# Stepper_2_0.net
KiCad netlist of a schematic drawn in EAGLE
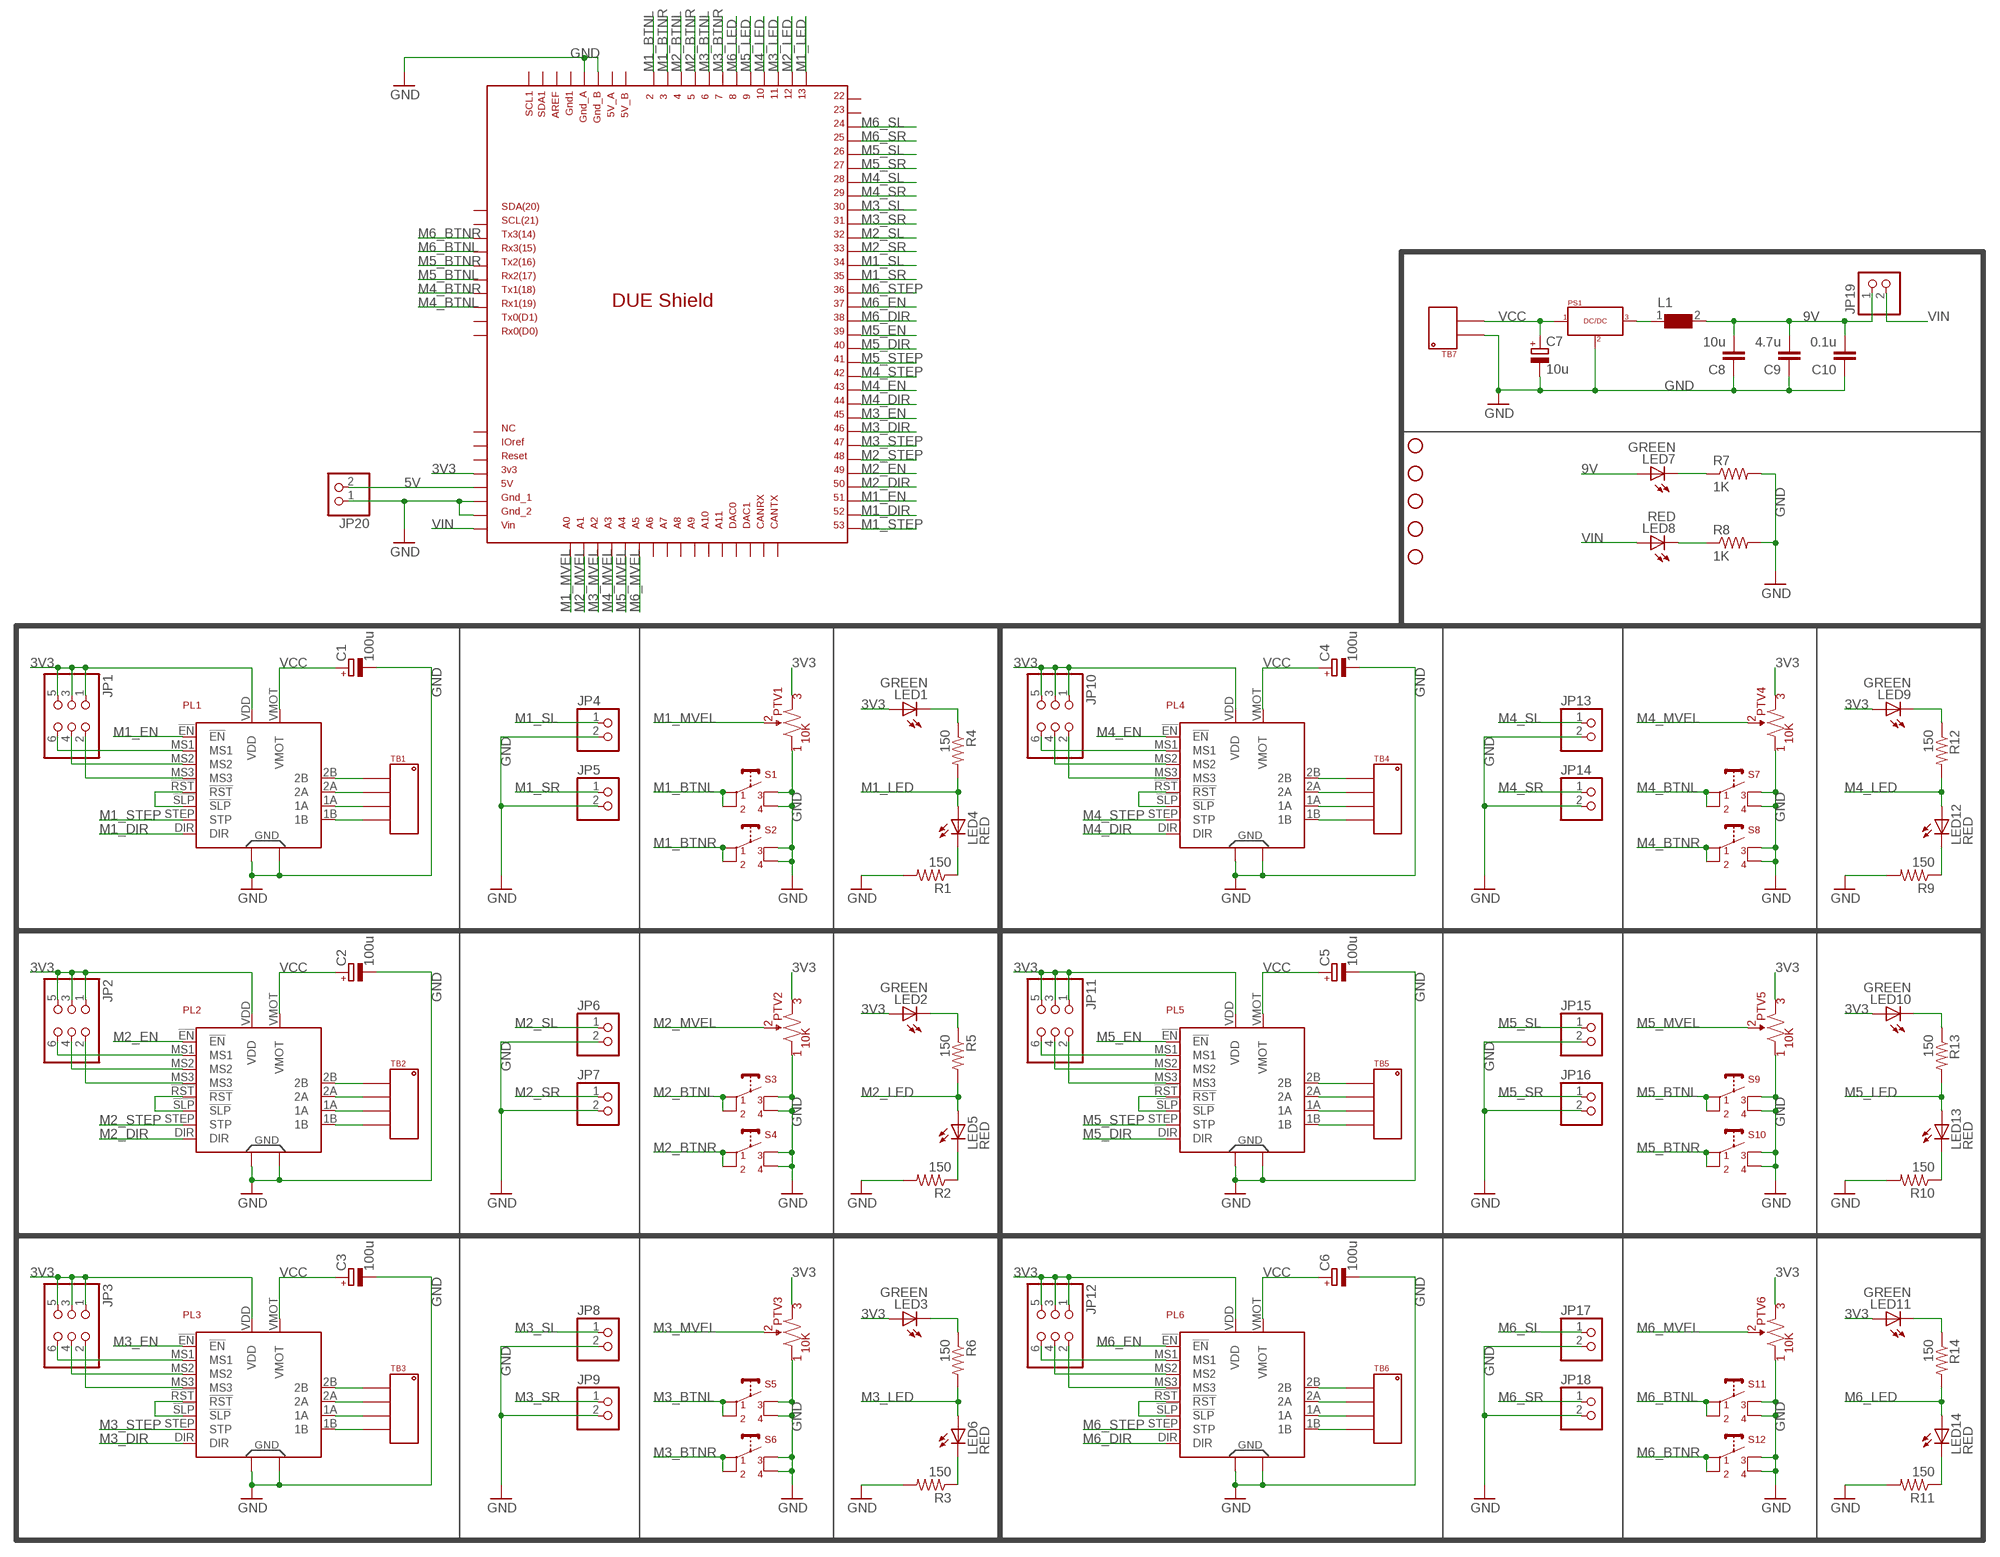
[diagram p0: schematic, sheet 1]

(export (version "E")
  (design (tool "Eeschema 10.0.6"))
  (components
    (comp (ref "C1")
      (value "100u")
      (footprint "eagle-import:ETR2")
      (libsource (lib "eagle-import") (part "CPOL-EUETR2"))
    )
    (comp (ref "C2")
      (value "100u")
      (footprint "eagle-import:ETR2")
      (libsource (lib "eagle-import") (part "CPOL-EUETR2"))
    )
    (comp (ref "C3")
      (value "100u")
      (footprint "eagle-import:ETR2")
      (libsource (lib "eagle-import") (part "CPOL-EUETR2"))
    )
    (comp (ref "C4")
      (value "100u")
      (footprint "eagle-import:ETR2")
      (libsource (lib "eagle-import") (part "CPOL-EUETR2"))
    )
    (comp (ref "C5")
      (value "100u")
      (footprint "eagle-import:ETR2")
      (libsource (lib "eagle-import") (part "CPOL-EUETR2"))
    )
    (comp (ref "C6")
      (value "100u")
      (footprint "eagle-import:ETR2")
      (libsource (lib "eagle-import") (part "CPOL-EUETR2"))
    )
    (comp (ref "C7")
      (value "10u")
      (footprint "eagle-import:E2-4")
      (libsource (lib "eagle-import") (part "CPOL-EUE2-4"))
    )
    (comp (ref "C8")
      (value "10u")
      (footprint "eagle-import:1206")
      (libsource (lib "eagle-import") (part "CAP1206"))
    )
    (comp (ref "C9")
      (value "4.7u")
      (footprint "eagle-import:1206")
      (libsource (lib "eagle-import") (part "CAP1206"))
    )
    (comp (ref "C10")
      (value "0.1u")
      (footprint "eagle-import:1206")
      (libsource (lib "eagle-import") (part "CAP1206"))
    )
    (comp (ref "DUE1")
      (value "DUE(NOSPI)")
      (footprint "eagle-import:DUE(NOSPI)")
      (libsource (lib "eagle-import") (part "DUE(NOSPI)"))
    )
    (comp (ref "H1")
      (value "STAND-OFF")
      (footprint "eagle-import:STAND-OFF")
      (libsource (lib "eagle-import") (part "STAND-OFF"))
    )
    (comp (ref "H2")
      (value "STAND-OFF")
      (footprint "eagle-import:STAND-OFF")
      (libsource (lib "eagle-import") (part "STAND-OFF"))
    )
    (comp (ref "H3")
      (value "STAND-OFF")
      (footprint "eagle-import:STAND-OFF")
      (libsource (lib "eagle-import") (part "STAND-OFF"))
    )
    (comp (ref "H4")
      (value "STAND-OFF")
      (footprint "eagle-import:STAND-OFF")
      (libsource (lib "eagle-import") (part "STAND-OFF"))
    )
    (comp (ref "H5")
      (value "STAND-OFF")
      (footprint "eagle-import:STAND-OFF")
      (libsource (lib "eagle-import") (part "STAND-OFF"))
    )
    (comp (ref "JP1")
      (value "PINHD-2X3")
      (footprint "eagle-import:2X03")
      (libsource (lib "eagle-import") (part "PINHD-2X3"))
    )
    (comp (ref "JP2")
      (value "PINHD-2X3")
      (footprint "eagle-import:2X03")
      (libsource (lib "eagle-import") (part "PINHD-2X3"))
    )
    (comp (ref "JP3")
      (value "PINHD-2X3")
      (footprint "eagle-import:2X03")
      (libsource (lib "eagle-import") (part "PINHD-2X3"))
    )
    (comp (ref "JP4")
      (value "PINHD-1X2")
      (footprint "eagle-import:1X02")
      (libsource (lib "eagle-import") (part "PINHD-1X2"))
    )
    (comp (ref "JP5")
      (value "PINHD-1X2")
      (footprint "eagle-import:1X02")
      (libsource (lib "eagle-import") (part "PINHD-1X2"))
    )
    (comp (ref "JP6")
      (value "PINHD-1X2")
      (footprint "eagle-import:1X02")
      (libsource (lib "eagle-import") (part "PINHD-1X2"))
    )
    (comp (ref "JP7")
      (value "PINHD-1X2")
      (footprint "eagle-import:1X02")
      (libsource (lib "eagle-import") (part "PINHD-1X2"))
    )
    (comp (ref "JP8")
      (value "PINHD-1X2")
      (footprint "eagle-import:1X02")
      (libsource (lib "eagle-import") (part "PINHD-1X2"))
    )
    (comp (ref "JP9")
      (value "PINHD-1X2")
      (footprint "eagle-import:1X02")
      (libsource (lib "eagle-import") (part "PINHD-1X2"))
    )
    (comp (ref "JP10")
      (value "PINHD-2X3")
      (footprint "eagle-import:2X03")
      (libsource (lib "eagle-import") (part "PINHD-2X3"))
    )
    (comp (ref "JP11")
      (value "PINHD-2X3")
      (footprint "eagle-import:2X03")
      (libsource (lib "eagle-import") (part "PINHD-2X3"))
    )
    (comp (ref "JP12")
      (value "PINHD-2X3")
      (footprint "eagle-import:2X03")
      (libsource (lib "eagle-import") (part "PINHD-2X3"))
    )
    (comp (ref "JP13")
      (value "PINHD-1X2")
      (footprint "eagle-import:1X02")
      (libsource (lib "eagle-import") (part "PINHD-1X2"))
    )
    (comp (ref "JP14")
      (value "PINHD-1X2")
      (footprint "eagle-import:1X02")
      (libsource (lib "eagle-import") (part "PINHD-1X2"))
    )
    (comp (ref "JP15")
      (value "PINHD-1X2")
      (footprint "eagle-import:1X02")
      (libsource (lib "eagle-import") (part "PINHD-1X2"))
    )
    (comp (ref "JP16")
      (value "PINHD-1X2")
      (footprint "eagle-import:1X02")
      (libsource (lib "eagle-import") (part "PINHD-1X2"))
    )
    (comp (ref "JP17")
      (value "PINHD-1X2")
      (footprint "eagle-import:1X02")
      (libsource (lib "eagle-import") (part "PINHD-1X2"))
    )
    (comp (ref "JP18")
      (value "PINHD-1X2")
      (footprint "eagle-import:1X02")
      (libsource (lib "eagle-import") (part "PINHD-1X2"))
    )
    (comp (ref "JP19")
      (value "PINHD-1X2")
      (footprint "eagle-import:1X02")
      (libsource (lib "eagle-import") (part "PINHD-1X2"))
    )
    (comp (ref "JP20")
      (value "PINHD-1X2")
      (footprint "eagle-import:1X02")
      (libsource (lib "eagle-import") (part "PINHD-1X2"))
    )
    (comp (ref "L1")
      (value "WE-CBF-742792118_1206")
      (footprint "eagle-import:1206")
      (fields (field (name "MPN") "742792118"))
      (libsource (lib "eagle-import") (part "WE-CBF_1206-742792118"))
    )
    (comp (ref "LED1")
      (value "GREEN")
      (footprint "eagle-import:1206")
      (libsource (lib "eagle-import") (part "LEDSMT1206"))
    )
    (comp (ref "LED2")
      (value "GREEN")
      (footprint "eagle-import:1206")
      (libsource (lib "eagle-import") (part "LEDSMT1206"))
    )
    (comp (ref "LED3")
      (value "GREEN")
      (footprint "eagle-import:1206")
      (libsource (lib "eagle-import") (part "LEDSMT1206"))
    )
    (comp (ref "LED4")
      (value "RED")
      (footprint "eagle-import:1206")
      (libsource (lib "eagle-import") (part "LEDSMT1206"))
    )
    (comp (ref "LED5")
      (value "RED")
      (footprint "eagle-import:1206")
      (libsource (lib "eagle-import") (part "LEDSMT1206"))
    )
    (comp (ref "LED6")
      (value "RED")
      (footprint "eagle-import:1206")
      (libsource (lib "eagle-import") (part "LEDSMT1206"))
    )
    (comp (ref "LED7")
      (value "GREEN")
      (footprint "eagle-import:1206")
      (libsource (lib "eagle-import") (part "LEDSMT1206"))
    )
    (comp (ref "LED8")
      (value "RED")
      (footprint "eagle-import:1206")
      (libsource (lib "eagle-import") (part "LEDSMT1206"))
    )
    (comp (ref "LED9")
      (value "GREEN")
      (footprint "eagle-import:1206")
      (libsource (lib "eagle-import") (part "LEDSMT1206"))
    )
    (comp (ref "LED10")
      (value "GREEN")
      (footprint "eagle-import:1206")
      (libsource (lib "eagle-import") (part "LEDSMT1206"))
    )
    (comp (ref "LED11")
      (value "GREEN")
      (footprint "eagle-import:1206")
      (libsource (lib "eagle-import") (part "LEDSMT1206"))
    )
    (comp (ref "LED12")
      (value "RED")
      (footprint "eagle-import:1206")
      (libsource (lib "eagle-import") (part "LEDSMT1206"))
    )
    (comp (ref "LED13")
      (value "RED")
      (footprint "eagle-import:1206")
      (libsource (lib "eagle-import") (part "LEDSMT1206"))
    )
    (comp (ref "LED14")
      (value "RED")
      (footprint "eagle-import:1206")
      (libsource (lib "eagle-import") (part "LEDSMT1206"))
    )
    (comp (ref "PL1")
      (value "A4988X")
      (footprint "eagle-import:MD09X")
      (libsource (lib "eagle-import") (part "A4988X"))
    )
    (comp (ref "PL2")
      (value "A4988X")
      (footprint "eagle-import:MD09X")
      (libsource (lib "eagle-import") (part "A4988X"))
    )
    (comp (ref "PL3")
      (value "A4988X")
      (footprint "eagle-import:MD09X")
      (libsource (lib "eagle-import") (part "A4988X"))
    )
    (comp (ref "PL4")
      (value "A4988X")
      (footprint "eagle-import:MD09X")
      (libsource (lib "eagle-import") (part "A4988X"))
    )
    (comp (ref "PL5")
      (value "A4988X")
      (footprint "eagle-import:MD09X")
      (libsource (lib "eagle-import") (part "A4988X"))
    )
    (comp (ref "PL6")
      (value "A4988X")
      (footprint "eagle-import:MD09X")
      (libsource (lib "eagle-import") (part "A4988X"))
    )
    (comp (ref "PS1")
      (value "VX78-500")
      (footprint "eagle-import:VX78-500")
      (libsource (lib "eagle-import") (part "VX78-500"))
    )
    (comp (ref "PTV1")
      (value "10K")
      (footprint "eagle-import:PTV09A-4")
      (libsource (lib "eagle-import") (part "PTV09A-4"))
    )
    (comp (ref "PTV2")
      (value "10K")
      (footprint "eagle-import:PTV09A-4")
      (libsource (lib "eagle-import") (part "PTV09A-4"))
    )
    (comp (ref "PTV3")
      (value "10K")
      (footprint "eagle-import:PTV09A-4")
      (libsource (lib "eagle-import") (part "PTV09A-4"))
    )
    (comp (ref "PTV4")
      (value "10K")
      (footprint "eagle-import:PTV09A-4")
      (libsource (lib "eagle-import") (part "PTV09A-4"))
    )
    (comp (ref "PTV5")
      (value "10K")
      (footprint "eagle-import:PTV09A-4")
      (libsource (lib "eagle-import") (part "PTV09A-4"))
    )
    (comp (ref "PTV6")
      (value "10K")
      (footprint "eagle-import:PTV09A-4")
      (libsource (lib "eagle-import") (part "PTV09A-4"))
    )
    (comp (ref "R1")
      (value "150")
      (footprint "eagle-import:1206")
      (libsource (lib "eagle-import") (part "RESISTOR1206"))
    )
    (comp (ref "R2")
      (value "150")
      (footprint "eagle-import:1206")
      (libsource (lib "eagle-import") (part "RESISTOR1206"))
    )
    (comp (ref "R3")
      (value "150")
      (footprint "eagle-import:1206")
      (libsource (lib "eagle-import") (part "RESISTOR1206"))
    )
    (comp (ref "R4")
      (value "150")
      (footprint "eagle-import:1206")
      (libsource (lib "eagle-import") (part "RESISTOR1206"))
    )
    (comp (ref "R5")
      (value "150")
      (footprint "eagle-import:1206")
      (libsource (lib "eagle-import") (part "RESISTOR1206"))
    )
    (comp (ref "R6")
      (value "150")
      (footprint "eagle-import:1206")
      (libsource (lib "eagle-import") (part "RESISTOR1206"))
    )
    (comp (ref "R7")
      (value "1K")
      (footprint "eagle-import:1206")
      (libsource (lib "eagle-import") (part "RESISTOR1206"))
    )
    (comp (ref "R8")
      (value "1K")
      (footprint "eagle-import:1206")
      (libsource (lib "eagle-import") (part "RESISTOR1206"))
    )
    (comp (ref "R9")
      (value "150")
      (footprint "eagle-import:1206")
      (libsource (lib "eagle-import") (part "RESISTOR1206"))
    )
    (comp (ref "R10")
      (value "150")
      (footprint "eagle-import:1206")
      (libsource (lib "eagle-import") (part "RESISTOR1206"))
    )
    (comp (ref "R11")
      (value "150")
      (footprint "eagle-import:1206")
      (libsource (lib "eagle-import") (part "RESISTOR1206"))
    )
    (comp (ref "R12")
      (value "150")
      (footprint "eagle-import:1206")
      (libsource (lib "eagle-import") (part "RESISTOR1206"))
    )
    (comp (ref "R13")
      (value "150")
      (footprint "eagle-import:1206")
      (libsource (lib "eagle-import") (part "RESISTOR1206"))
    )
    (comp (ref "R14")
      (value "150")
      (footprint "eagle-import:1206")
      (libsource (lib "eagle-import") (part "RESISTOR1206"))
    )
    (comp (ref "S1")
      (value "BTN_SPST_6MM")
      (footprint "eagle-import:BTN_SPST_6MM")
      (libsource (lib "eagle-import") (part "BTN_SPST_6MM"))
    )
    (comp (ref "S2")
      (value "BTN_SPST_6MM")
      (footprint "eagle-import:BTN_SPST_6MM")
      (libsource (lib "eagle-import") (part "BTN_SPST_6MM"))
    )
    (comp (ref "S3")
      (value "BTN_SPST_6MM")
      (footprint "eagle-import:BTN_SPST_6MM")
      (libsource (lib "eagle-import") (part "BTN_SPST_6MM"))
    )
    (comp (ref "S4")
      (value "BTN_SPST_6MM")
      (footprint "eagle-import:BTN_SPST_6MM")
      (libsource (lib "eagle-import") (part "BTN_SPST_6MM"))
    )
    (comp (ref "S5")
      (value "BTN_SPST_6MM")
      (footprint "eagle-import:BTN_SPST_6MM")
      (libsource (lib "eagle-import") (part "BTN_SPST_6MM"))
    )
    (comp (ref "S6")
      (value "BTN_SPST_6MM")
      (footprint "eagle-import:BTN_SPST_6MM")
      (libsource (lib "eagle-import") (part "BTN_SPST_6MM"))
    )
    (comp (ref "S7")
      (value "BTN_SPST_6MM")
      (footprint "eagle-import:BTN_SPST_6MM")
      (libsource (lib "eagle-import") (part "BTN_SPST_6MM"))
    )
    (comp (ref "S8")
      (value "BTN_SPST_6MM")
      (footprint "eagle-import:BTN_SPST_6MM")
      (libsource (lib "eagle-import") (part "BTN_SPST_6MM"))
    )
    (comp (ref "S9")
      (value "BTN_SPST_6MM")
      (footprint "eagle-import:BTN_SPST_6MM")
      (libsource (lib "eagle-import") (part "BTN_SPST_6MM"))
    )
    (comp (ref "S10")
      (value "BTN_SPST_6MM")
      (footprint "eagle-import:BTN_SPST_6MM")
      (libsource (lib "eagle-import") (part "BTN_SPST_6MM"))
    )
    (comp (ref "S11")
      (value "BTN_SPST_6MM")
      (footprint "eagle-import:BTN_SPST_6MM")
      (libsource (lib "eagle-import") (part "BTN_SPST_6MM"))
    )
    (comp (ref "S12")
      (value "BTN_SPST_6MM")
      (footprint "eagle-import:BTN_SPST_6MM")
      (libsource (lib "eagle-import") (part "BTN_SPST_6MM"))
    )
    (comp (ref "TB1")
      (value "TB_HEAD_3.5MM_01X04")
      (footprint "eagle-import:TB_HEAD_3.5MM_01X04")
      (libsource (lib "eagle-import") (part "TB_HEAD_3.5MM_01X04"))
    )
    (comp (ref "TB2")
      (value "TB_HEAD_3.5MM_01X04")
      (footprint "eagle-import:TB_HEAD_3.5MM_01X04")
      (libsource (lib "eagle-import") (part "TB_HEAD_3.5MM_01X04"))
    )
    (comp (ref "TB3")
      (value "TB_HEAD_3.5MM_01X04")
      (footprint "eagle-import:TB_HEAD_3.5MM_01X04")
      (libsource (lib "eagle-import") (part "TB_HEAD_3.5MM_01X04"))
    )
    (comp (ref "TB4")
      (value "TB_HEAD_3.5MM_01X04")
      (footprint "eagle-import:TB_HEAD_3.5MM_01X04")
      (libsource (lib "eagle-import") (part "TB_HEAD_3.5MM_01X04"))
    )
    (comp (ref "TB5")
      (value "TB_HEAD_3.5MM_01X04")
      (footprint "eagle-import:TB_HEAD_3.5MM_01X04")
      (libsource (lib "eagle-import") (part "TB_HEAD_3.5MM_01X04"))
    )
    (comp (ref "TB6")
      (value "TB_HEAD_3.5MM_01X04")
      (footprint "eagle-import:TB_HEAD_3.5MM_01X04")
      (libsource (lib "eagle-import") (part "TB_HEAD_3.5MM_01X04"))
    )
    (comp (ref "TB7")
      (value "TB_HEAD_3.5MM_01X02")
      (footprint "eagle-import:TB_HEAD_3.5MM_01X02")
      (libsource (lib "eagle-import") (part "TB_HEAD_3.5MM_01X02"))
    )
  )
  (nets
    (net (code "1") (name "/3V3") (class "Default")
      (node (ref "DUE1") (pin "3V3") (pinfunction "3V3_3V3") (pintype "bidirectional"))
      (node (ref "JP1") (pin "1") (pinfunction "1_1") (pintype "passive"))
      (node (ref "JP1") (pin "3") (pinfunction "3_3") (pintype "passive"))
      (node (ref "JP1") (pin "5") (pinfunction "5_5") (pintype "passive"))
      (node (ref "JP10") (pin "1") (pinfunction "1_1") (pintype "passive"))
      (node (ref "JP10") (pin "3") (pinfunction "3_3") (pintype "passive"))
      (node (ref "JP10") (pin "5") (pinfunction "5_5") (pintype "passive"))
      (node (ref "JP11") (pin "1") (pinfunction "1_1") (pintype "passive"))
      (node (ref "JP11") (pin "3") (pinfunction "3_3") (pintype "passive"))
      (node (ref "JP11") (pin "5") (pinfunction "5_5") (pintype "passive"))
      (node (ref "JP12") (pin "1") (pinfunction "1_1") (pintype "passive"))
      (node (ref "JP12") (pin "3") (pinfunction "3_3") (pintype "passive"))
      (node (ref "JP12") (pin "5") (pinfunction "5_5") (pintype "passive"))
      (node (ref "JP2") (pin "1") (pinfunction "1_1") (pintype "passive"))
      (node (ref "JP2") (pin "3") (pinfunction "3_3") (pintype "passive"))
      (node (ref "JP2") (pin "5") (pinfunction "5_5") (pintype "passive"))
      (node (ref "JP3") (pin "1") (pinfunction "1_1") (pintype "passive"))
      (node (ref "JP3") (pin "3") (pinfunction "3_3") (pintype "passive"))
      (node (ref "JP3") (pin "5") (pinfunction "5_5") (pintype "passive"))
      (node (ref "LED1") (pin "A") (pinfunction "A_A") (pintype "passive"))
      (node (ref "LED10") (pin "A") (pinfunction "A_A") (pintype "passive"))
      (node (ref "LED11") (pin "A") (pinfunction "A_A") (pintype "passive"))
      (node (ref "LED2") (pin "A") (pinfunction "A_A") (pintype "passive"))
      (node (ref "LED3") (pin "A") (pinfunction "A_A") (pintype "passive"))
      (node (ref "LED9") (pin "A") (pinfunction "A_A") (pintype "passive"))
      (node (ref "PL1") (pin "VDD") (pinfunction "VDD_VDD") (pintype "bidirectional"))
      (node (ref "PL2") (pin "VDD") (pinfunction "VDD_VDD") (pintype "bidirectional"))
      (node (ref "PL3") (pin "VDD") (pinfunction "VDD_VDD") (pintype "bidirectional"))
      (node (ref "PL4") (pin "VDD") (pinfunction "VDD_VDD") (pintype "bidirectional"))
      (node (ref "PL5") (pin "VDD") (pinfunction "VDD_VDD") (pintype "bidirectional"))
      (node (ref "PL6") (pin "VDD") (pinfunction "VDD_VDD") (pintype "bidirectional"))
      (node (ref "PTV1") (pin "P$3") (pinfunction "3_P$3") (pintype "bidirectional"))
      (node (ref "PTV2") (pin "P$3") (pinfunction "3_P$3") (pintype "bidirectional"))
      (node (ref "PTV3") (pin "P$3") (pinfunction "3_P$3") (pintype "bidirectional"))
      (node (ref "PTV4") (pin "P$3") (pinfunction "3_P$3") (pintype "bidirectional"))
      (node (ref "PTV5") (pin "P$3") (pinfunction "3_P$3") (pintype "bidirectional"))
      (node (ref "PTV6") (pin "P$3") (pinfunction "3_P$3") (pintype "bidirectional"))
    )
    (net (code "2") (name "/5V") (class "Default")
      (node (ref "DUE1") (pin "5V") (pinfunction "5V_5V") (pintype "bidirectional"))
      (node (ref "JP20") (pin "2") (pinfunction "2_2") (pintype "passive"))
    )
    (net (code "3") (name "/9V") (class "Default")
      (node (ref "C10") (pin "2") (pinfunction "2_2") (pintype "passive"))
      (node (ref "C8") (pin "2") (pinfunction "2_2") (pintype "passive"))
      (node (ref "C9") (pin "2") (pinfunction "2_2") (pintype "passive"))
      (node (ref "JP19") (pin "1") (pinfunction "1_1") (pintype "passive"))
      (node (ref "L1") (pin "2") (pinfunction "2_2") (pintype "passive"))
      (node (ref "LED7") (pin "A") (pinfunction "A_A") (pintype "passive"))
    )
    (net (code "4") (name "/M1_BTNL") (class "Default")
      (node (ref "DUE1") (pin "2") (pinfunction "2_2") (pintype "bidirectional"))
      (node (ref "S1") (pin "P$1") (pinfunction "1_P$1") (pintype "bidirectional"))
      (node (ref "S1") (pin "P$2") (pinfunction "2_P$2") (pintype "bidirectional"))
    )
    (net (code "5") (name "/M1_BTNR") (class "Default")
      (node (ref "DUE1") (pin "3") (pinfunction "3_3") (pintype "bidirectional"))
      (node (ref "S2") (pin "P$1") (pinfunction "1_P$1") (pintype "bidirectional"))
      (node (ref "S2") (pin "P$2") (pinfunction "2_P$2") (pintype "bidirectional"))
    )
    (net (code "6") (name "/M1_DIR") (class "Default")
      (node (ref "DUE1") (pin "52") (pinfunction "52_52") (pintype "bidirectional"))
      (node (ref "PL1") (pin "DIR") (pinfunction "DIR_DIR") (pintype "bidirectional"))
    )
    (net (code "7") (name "/M1_EN") (class "Default")
      (node (ref "DUE1") (pin "51") (pinfunction "51_51") (pintype "bidirectional"))
      (node (ref "PL1") (pin "!EN") (pinfunction "~{EN}_!EN") (pintype "bidirectional"))
    )
    (net (code "8") (name "/M1_LED") (class "Default")
      (node (ref "DUE1") (pin "13") (pinfunction "13_13") (pintype "bidirectional"))
      (node (ref "LED4") (pin "A") (pinfunction "A_A") (pintype "passive"))
      (node (ref "R4") (pin "2") (pinfunction "2_2") (pintype "passive"))
    )
    (net (code "9") (name "/M1_MVEL") (class "Default")
      (node (ref "DUE1") (pin "A0") (pinfunction "A0_A0") (pintype "bidirectional"))
      (node (ref "PTV1") (pin "P$2") (pinfunction "2_P$2") (pintype "bidirectional"))
    )
    (net (code "10") (name "/M1_SL") (class "Default")
      (node (ref "DUE1") (pin "34") (pinfunction "34_34") (pintype "bidirectional"))
      (node (ref "JP4") (pin "1") (pinfunction "1_1") (pintype "passive"))
    )
    (net (code "11") (name "/M1_SR") (class "Default")
      (node (ref "DUE1") (pin "35") (pinfunction "35_35") (pintype "bidirectional"))
      (node (ref "JP5") (pin "1") (pinfunction "1_1") (pintype "passive"))
    )
    (net (code "12") (name "/M1_STEP") (class "Default")
      (node (ref "DUE1") (pin "53") (pinfunction "53_53") (pintype "bidirectional"))
      (node (ref "PL1") (pin "STEP") (pinfunction "STP_STEP") (pintype "bidirectional"))
    )
    (net (code "13") (name "/M2_BTNL") (class "Default")
      (node (ref "DUE1") (pin "4") (pinfunction "4_4") (pintype "bidirectional"))
      (node (ref "S3") (pin "P$1") (pinfunction "1_P$1") (pintype "bidirectional"))
      (node (ref "S3") (pin "P$2") (pinfunction "2_P$2") (pintype "bidirectional"))
    )
    (net (code "14") (name "/M2_BTNR") (class "Default")
      (node (ref "DUE1") (pin "5") (pinfunction "5_5") (pintype "bidirectional"))
      (node (ref "S4") (pin "P$1") (pinfunction "1_P$1") (pintype "bidirectional"))
      (node (ref "S4") (pin "P$2") (pinfunction "2_P$2") (pintype "bidirectional"))
    )
    (net (code "15") (name "/M2_DIR") (class "Default")
      (node (ref "DUE1") (pin "50") (pinfunction "50_50") (pintype "bidirectional"))
      (node (ref "PL2") (pin "DIR") (pinfunction "DIR_DIR") (pintype "bidirectional"))
    )
    (net (code "16") (name "/M2_EN") (class "Default")
      (node (ref "DUE1") (pin "49") (pinfunction "49_49") (pintype "bidirectional"))
      (node (ref "PL2") (pin "!EN") (pinfunction "~{EN}_!EN") (pintype "bidirectional"))
    )
    (net (code "17") (name "/M2_LED") (class "Default")
      (node (ref "DUE1") (pin "12") (pinfunction "12_12") (pintype "bidirectional"))
      (node (ref "LED5") (pin "A") (pinfunction "A_A") (pintype "passive"))
      (node (ref "R5") (pin "2") (pinfunction "2_2") (pintype "passive"))
    )
    (net (code "18") (name "/M2_MVEL") (class "Default")
      (node (ref "DUE1") (pin "A1") (pinfunction "A1_A1") (pintype "bidirectional"))
      (node (ref "PTV2") (pin "P$2") (pinfunction "2_P$2") (pintype "bidirectional"))
    )
    (net (code "19") (name "/M2_SL") (class "Default")
      (node (ref "DUE1") (pin "32") (pinfunction "32_32") (pintype "bidirectional"))
      (node (ref "JP6") (pin "1") (pinfunction "1_1") (pintype "passive"))
    )
    (net (code "20") (name "/M2_SR") (class "Default")
      (node (ref "DUE1") (pin "33") (pinfunction "33_33") (pintype "bidirectional"))
      (node (ref "JP7") (pin "1") (pinfunction "1_1") (pintype "passive"))
    )
    (net (code "21") (name "/M2_STEP") (class "Default")
      (node (ref "DUE1") (pin "48") (pinfunction "48_48") (pintype "bidirectional"))
      (node (ref "PL2") (pin "STEP") (pinfunction "STP_STEP") (pintype "bidirectional"))
    )
    (net (code "22") (name "/M3_BTNL") (class "Default")
      (node (ref "DUE1") (pin "6") (pinfunction "6_6") (pintype "bidirectional"))
      (node (ref "S5") (pin "P$1") (pinfunction "1_P$1") (pintype "bidirectional"))
      (node (ref "S5") (pin "P$2") (pinfunction "2_P$2") (pintype "bidirectional"))
    )
    (net (code "23") (name "/M3_BTNR") (class "Default")
      (node (ref "DUE1") (pin "7") (pinfunction "7_7") (pintype "bidirectional"))
      (node (ref "S6") (pin "P$1") (pinfunction "1_P$1") (pintype "bidirectional"))
      (node (ref "S6") (pin "P$2") (pinfunction "2_P$2") (pintype "bidirectional"))
    )
    (net (code "24") (name "/M3_DIR") (class "Default")
      (node (ref "DUE1") (pin "46") (pinfunction "46_46") (pintype "bidirectional"))
      (node (ref "PL3") (pin "DIR") (pinfunction "DIR_DIR") (pintype "bidirectional"))
    )
    (net (code "25") (name "/M3_EN") (class "Default")
      (node (ref "DUE1") (pin "45") (pinfunction "45_45") (pintype "bidirectional"))
      (node (ref "PL3") (pin "!EN") (pinfunction "~{EN}_!EN") (pintype "bidirectional"))
    )
    (net (code "26") (name "/M3_LED") (class "Default")
      (node (ref "DUE1") (pin "11") (pinfunction "11_11") (pintype "bidirectional"))
      (node (ref "LED6") (pin "A") (pinfunction "A_A") (pintype "passive"))
      (node (ref "R6") (pin "2") (pinfunction "2_2") (pintype "passive"))
    )
    (net (code "27") (name "/M3_MVEL") (class "Default")
      (node (ref "DUE1") (pin "A2") (pinfunction "A2_A2") (pintype "bidirectional"))
      (node (ref "PTV3") (pin "P$2") (pinfunction "2_P$2") (pintype "bidirectional"))
    )
    (net (code "28") (name "/M3_SL") (class "Default")
      (node (ref "DUE1") (pin "30") (pinfunction "30_30") (pintype "bidirectional"))
      (node (ref "JP8") (pin "1") (pinfunction "1_1") (pintype "passive"))
    )
    (net (code "29") (name "/M3_SR") (class "Default")
      (node (ref "DUE1") (pin "31") (pinfunction "31_31") (pintype "bidirectional"))
      (node (ref "JP9") (pin "1") (pinfunction "1_1") (pintype "passive"))
    )
    (net (code "30") (name "/M3_STEP") (class "Default")
      (node (ref "DUE1") (pin "47") (pinfunction "47_47") (pintype "bidirectional"))
      (node (ref "PL3") (pin "STEP") (pinfunction "STP_STEP") (pintype "bidirectional"))
    )
    (net (code "31") (name "/M4_BTNL") (class "Default")
      (node (ref "DUE1") (pin "RX1") (pinfunction "RX1_RX1") (pintype "bidirectional"))
      (node (ref "S7") (pin "P$1") (pinfunction "1_P$1") (pintype "bidirectional"))
      (node (ref "S7") (pin "P$2") (pinfunction "2_P$2") (pintype "bidirectional"))
    )
    (net (code "32") (name "/M4_BTNR") (class "Default")
      (node (ref "DUE1") (pin "TX1") (pinfunction "TX1_TX1") (pintype "bidirectional"))
      (node (ref "S8") (pin "P$1") (pinfunction "1_P$1") (pintype "bidirectional"))
      (node (ref "S8") (pin "P$2") (pinfunction "2_P$2") (pintype "bidirectional"))
    )
    (net (code "33") (name "/M4_DIR") (class "Default")
      (node (ref "DUE1") (pin "44") (pinfunction "44_44") (pintype "bidirectional"))
      (node (ref "PL4") (pin "DIR") (pinfunction "DIR_DIR") (pintype "bidirectional"))
    )
    (net (code "34") (name "/M4_EN") (class "Default")
      (node (ref "DUE1") (pin "43") (pinfunction "43_43") (pintype "bidirectional"))
      (node (ref "PL4") (pin "!EN") (pinfunction "~{EN}_!EN") (pintype "bidirectional"))
    )
    (net (code "35") (name "/M4_LED") (class "Default")
      (node (ref "DUE1") (pin "10") (pinfunction "10_10") (pintype "bidirectional"))
      (node (ref "LED12") (pin "A") (pinfunction "A_A") (pintype "passive"))
      (node (ref "R12") (pin "2") (pinfunction "2_2") (pintype "passive"))
    )
    (net (code "36") (name "/M4_MVEL") (class "Default")
      (node (ref "DUE1") (pin "A3") (pinfunction "A3_A3") (pintype "bidirectional"))
      (node (ref "PTV4") (pin "P$2") (pinfunction "2_P$2") (pintype "bidirectional"))
    )
    (net (code "37") (name "/M4_SL") (class "Default")
      (node (ref "DUE1") (pin "28") (pinfunction "28_28") (pintype "bidirectional"))
      (node (ref "JP13") (pin "1") (pinfunction "1_1") (pintype "passive"))
    )
    (net (code "38") (name "/M4_SR") (class "Default")
      (node (ref "DUE1") (pin "29") (pinfunction "29_29") (pintype "bidirectional"))
      (node (ref "JP14") (pin "1") (pinfunction "1_1") (pintype "passive"))
    )
    (net (code "39") (name "/M4_STEP") (class "Default")
      (node (ref "DUE1") (pin "42") (pinfunction "42_42") (pintype "bidirectional"))
      (node (ref "PL4") (pin "STEP") (pinfunction "STP_STEP") (pintype "bidirectional"))
    )
    (net (code "40") (name "/M5_BTNL") (class "Default")
      (node (ref "DUE1") (pin "RX2") (pinfunction "RX2_RX2") (pintype "bidirectional"))
      (node (ref "S9") (pin "P$1") (pinfunction "1_P$1") (pintype "bidirectional"))
      (node (ref "S9") (pin "P$2") (pinfunction "2_P$2") (pintype "bidirectional"))
    )
    (net (code "41") (name "/M5_BTNR") (class "Default")
      (node (ref "DUE1") (pin "TX2") (pinfunction "TX2_TX2") (pintype "bidirectional"))
      (node (ref "S10") (pin "P$1") (pinfunction "1_P$1") (pintype "bidirectional"))
      (node (ref "S10") (pin "P$2") (pinfunction "2_P$2") (pintype "bidirectional"))
    )
    (net (code "42") (name "/M5_DIR") (class "Default")
      (node (ref "DUE1") (pin "40") (pinfunction "40_40") (pintype "bidirectional"))
      (node (ref "PL5") (pin "DIR") (pinfunction "DIR_DIR") (pintype "bidirectional"))
    )
    (net (code "43") (name "/M5_EN") (class "Default")
      (node (ref "DUE1") (pin "39") (pinfunction "39_39") (pintype "bidirectional"))
      (node (ref "PL5") (pin "!EN") (pinfunction "~{EN}_!EN") (pintype "bidirectional"))
    )
    (net (code "44") (name "/M5_LED") (class "Default")
      (node (ref "DUE1") (pin "9") (pinfunction "9_9") (pintype "bidirectional"))
      (node (ref "LED13") (pin "A") (pinfunction "A_A") (pintype "passive"))
      (node (ref "R13") (pin "2") (pinfunction "2_2") (pintype "passive"))
    )
    (net (code "45") (name "/M5_MVEL") (class "Default")
      (node (ref "DUE1") (pin "A4") (pinfunction "A4_A4") (pintype "bidirectional"))
      (node (ref "PTV5") (pin "P$2") (pinfunction "2_P$2") (pintype "bidirectional"))
    )
    (net (code "46") (name "/M5_SL") (class "Default")
      (node (ref "DUE1") (pin "26") (pinfunction "26_26") (pintype "bidirectional"))
      (node (ref "JP15") (pin "1") (pinfunction "1_1") (pintype "passive"))
    )
    (net (code "47") (name "/M5_SR") (class "Default")
      (node (ref "DUE1") (pin "27") (pinfunction "27_27") (pintype "bidirectional"))
      (node (ref "JP16") (pin "1") (pinfunction "1_1") (pintype "passive"))
    )
    (net (code "48") (name "/M5_STEP") (class "Default")
      (node (ref "DUE1") (pin "41") (pinfunction "41_41") (pintype "bidirectional"))
      (node (ref "PL5") (pin "STEP") (pinfunction "STP_STEP") (pintype "bidirectional"))
    )
    (net (code "49") (name "/M6_BTNL") (class "Default")
      (node (ref "DUE1") (pin "RX3") (pinfunction "RX3_RX3") (pintype "bidirectional"))
      (node (ref "S11") (pin "P$1") (pinfunction "1_P$1") (pintype "bidirectional"))
      (node (ref "S11") (pin "P$2") (pinfunction "2_P$2") (pintype "bidirectional"))
    )
    (net (code "50") (name "/M6_BTNR") (class "Default")
      (node (ref "DUE1") (pin "TX3") (pinfunction "TX3_TX3") (pintype "bidirectional"))
      (node (ref "S12") (pin "P$1") (pinfunction "1_P$1") (pintype "bidirectional"))
      (node (ref "S12") (pin "P$2") (pinfunction "2_P$2") (pintype "bidirectional"))
    )
    (net (code "51") (name "/M6_DIR") (class "Default")
      (node (ref "DUE1") (pin "38") (pinfunction "38_38") (pintype "bidirectional"))
      (node (ref "PL6") (pin "DIR") (pinfunction "DIR_DIR") (pintype "bidirectional"))
    )
    (net (code "52") (name "/M6_EN") (class "Default")
      (node (ref "DUE1") (pin "37") (pinfunction "37_37") (pintype "bidirectional"))
      (node (ref "PL6") (pin "!EN") (pinfunction "~{EN}_!EN") (pintype "bidirectional"))
    )
    (net (code "53") (name "/M6_LED") (class "Default")
      (node (ref "DUE1") (pin "8") (pinfunction "8_8") (pintype "bidirectional"))
      (node (ref "LED14") (pin "A") (pinfunction "A_A") (pintype "passive"))
      (node (ref "R14") (pin "2") (pinfunction "2_2") (pintype "passive"))
    )
    (net (code "54") (name "/M6_MVEL") (class "Default")
      (node (ref "DUE1") (pin "A5") (pinfunction "A5_A5") (pintype "bidirectional"))
      (node (ref "PTV6") (pin "P$2") (pinfunction "2_P$2") (pintype "bidirectional"))
    )
    (net (code "55") (name "/M6_SL") (class "Default")
      (node (ref "DUE1") (pin "24") (pinfunction "24_24") (pintype "bidirectional"))
      (node (ref "JP17") (pin "1") (pinfunction "1_1") (pintype "passive"))
    )
    (net (code "56") (name "/M6_SR") (class "Default")
      (node (ref "DUE1") (pin "25") (pinfunction "25_25") (pintype "bidirectional"))
      (node (ref "JP18") (pin "1") (pinfunction "1_1") (pintype "passive"))
    )
    (net (code "57") (name "/M6_STEP") (class "Default")
      (node (ref "DUE1") (pin "36") (pinfunction "36_36") (pintype "bidirectional"))
      (node (ref "PL6") (pin "STEP") (pinfunction "STP_STEP") (pintype "bidirectional"))
    )
    (net (code "58") (name "/VCC") (class "Default")
      (node (ref "C1") (pin "+") (pinfunction "+_+") (pintype "passive"))
      (node (ref "C2") (pin "+") (pinfunction "+_+") (pintype "passive"))
      (node (ref "C3") (pin "+") (pinfunction "+_+") (pintype "passive"))
      (node (ref "C4") (pin "+") (pinfunction "+_+") (pintype "passive"))
      (node (ref "C5") (pin "+") (pinfunction "+_+") (pintype "passive"))
      (node (ref "C6") (pin "+") (pinfunction "+_+") (pintype "passive"))
      (node (ref "C7") (pin "+") (pinfunction "+_+") (pintype "passive"))
      (node (ref "PL1") (pin "VMOT") (pinfunction "VMOT_VMOT") (pintype "bidirectional"))
      (node (ref "PL2") (pin "VMOT") (pinfunction "VMOT_VMOT") (pintype "bidirectional"))
      (node (ref "PL3") (pin "VMOT") (pinfunction "VMOT_VMOT") (pintype "bidirectional"))
      (node (ref "PL4") (pin "VMOT") (pinfunction "VMOT_VMOT") (pintype "bidirectional"))
      (node (ref "PL5") (pin "VMOT") (pinfunction "VMOT_VMOT") (pintype "bidirectional"))
      (node (ref "PL6") (pin "VMOT") (pinfunction "VMOT_VMOT") (pintype "bidirectional"))
      (node (ref "PS1") (pin "P$1") (pinfunction "P$1_P$1") (pintype "bidirectional"))
      (node (ref "TB7") (pin "P$2") (pinfunction "P$3_P$2") (pintype "bidirectional"))
    )
    (net (code "59") (name "/VIN") (class "Default")
      (node (ref "DUE1") (pin "VIN") (pinfunction "VIN_VIN") (pintype "bidirectional"))
      (node (ref "JP19") (pin "2") (pinfunction "2_2") (pintype "passive"))
      (node (ref "LED8") (pin "A") (pinfunction "A_A") (pintype "passive"))
    )
    (net (code "60") (name "GND") (class "Default")
      (node (ref "C1") (pin "-") (pinfunction "-_-") (pintype "passive"))
      (node (ref "C10") (pin "1") (pinfunction "1_1") (pintype "passive"))
      (node (ref "C2") (pin "-") (pinfunction "-_-") (pintype "passive"))
      (node (ref "C3") (pin "-") (pinfunction "-_-") (pintype "passive"))
      (node (ref "C4") (pin "-") (pinfunction "-_-") (pintype "passive"))
      (node (ref "C5") (pin "-") (pinfunction "-_-") (pintype "passive"))
      (node (ref "C6") (pin "-") (pinfunction "-_-") (pintype "passive"))
      (node (ref "C7") (pin "-") (pinfunction "-_-") (pintype "passive"))
      (node (ref "C8") (pin "1") (pinfunction "1_1") (pintype "passive"))
      (node (ref "C9") (pin "1") (pinfunction "1_1") (pintype "passive"))
      (node (ref "DUE1") (pin "GND_1") (pinfunction "GND_1_GND_1") (pintype "bidirectional"))
      (node (ref "DUE1") (pin "GND_2") (pinfunction "GND_2_GND_2") (pintype "bidirectional"))
      (node (ref "DUE1") (pin "GND_A") (pinfunction "GND_A_GND_A") (pintype "bidirectional"))
      (node (ref "DUE1") (pin "GND_B") (pinfunction "GND_B_GND_B") (pintype "bidirectional"))
      (node (ref "JP13") (pin "2") (pinfunction "2_2") (pintype "passive"))
      (node (ref "JP14") (pin "2") (pinfunction "2_2") (pintype "passive"))
      (node (ref "JP15") (pin "2") (pinfunction "2_2") (pintype "passive"))
      (node (ref "JP16") (pin "2") (pinfunction "2_2") (pintype "passive"))
      (node (ref "JP17") (pin "2") (pinfunction "2_2") (pintype "passive"))
      (node (ref "JP18") (pin "2") (pinfunction "2_2") (pintype "passive"))
      (node (ref "JP20") (pin "1") (pinfunction "1_1") (pintype "passive"))
      (node (ref "JP4") (pin "2") (pinfunction "2_2") (pintype "passive"))
      (node (ref "JP5") (pin "2") (pinfunction "2_2") (pintype "passive"))
      (node (ref "JP6") (pin "2") (pinfunction "2_2") (pintype "passive"))
      (node (ref "JP7") (pin "2") (pinfunction "2_2") (pintype "passive"))
      (node (ref "JP8") (pin "2") (pinfunction "2_2") (pintype "passive"))
      (node (ref "JP9") (pin "2") (pinfunction "2_2") (pintype "passive"))
      (node (ref "PL1") (pin "GND1") (pinfunction "GND1_GND1") (pintype "bidirectional"))
      (node (ref "PL1") (pin "GND2") (pinfunction "GND2_GND2") (pintype "bidirectional"))
      (node (ref "PL2") (pin "GND1") (pinfunction "GND1_GND1") (pintype "bidirectional"))
      (node (ref "PL2") (pin "GND2") (pinfunction "GND2_GND2") (pintype "bidirectional"))
      (node (ref "PL3") (pin "GND1") (pinfunction "GND1_GND1") (pintype "bidirectional"))
      (node (ref "PL3") (pin "GND2") (pinfunction "GND2_GND2") (pintype "bidirectional"))
      (node (ref "PL4") (pin "GND1") (pinfunction "GND1_GND1") (pintype "bidirectional"))
      (node (ref "PL4") (pin "GND2") (pinfunction "GND2_GND2") (pintype "bidirectional"))
      (node (ref "PL5") (pin "GND1") (pinfunction "GND1_GND1") (pintype "bidirectional"))
      (node (ref "PL5") (pin "GND2") (pinfunction "GND2_GND2") (pintype "bidirectional"))
      (node (ref "PL6") (pin "GND1") (pinfunction "GND1_GND1") (pintype "bidirectional"))
      (node (ref "PL6") (pin "GND2") (pinfunction "GND2_GND2") (pintype "bidirectional"))
      (node (ref "PS1") (pin "P$3") (pinfunction "P$3_P$3") (pintype "bidirectional"))
      (node (ref "PTV1") (pin "P$1") (pinfunction "1_P$1") (pintype "bidirectional"))
      (node (ref "PTV2") (pin "P$1") (pinfunction "1_P$1") (pintype "bidirectional"))
      (node (ref "PTV3") (pin "P$1") (pinfunction "1_P$1") (pintype "bidirectional"))
      (node (ref "PTV4") (pin "P$1") (pinfunction "1_P$1") (pintype "bidirectional"))
      (node (ref "PTV5") (pin "P$1") (pinfunction "1_P$1") (pintype "bidirectional"))
      (node (ref "PTV6") (pin "P$1") (pinfunction "1_P$1") (pintype "bidirectional"))
      (node (ref "R1") (pin "2") (pinfunction "2_2") (pintype "passive"))
      (node (ref "R10") (pin "2") (pinfunction "2_2") (pintype "passive"))
      (node (ref "R11") (pin "2") (pinfunction "2_2") (pintype "passive"))
      (node (ref "R2") (pin "2") (pinfunction "2_2") (pintype "passive"))
      (node (ref "R3") (pin "2") (pinfunction "2_2") (pintype "passive"))
      (node (ref "R7") (pin "2") (pinfunction "2_2") (pintype "passive"))
      (node (ref "R8") (pin "2") (pinfunction "2_2") (pintype "passive"))
      (node (ref "R9") (pin "2") (pinfunction "2_2") (pintype "passive"))
      (node (ref "S1") (pin "P$3") (pinfunction "3_P$3") (pintype "bidirectional"))
      (node (ref "S1") (pin "P$4") (pinfunction "4_P$4") (pintype "bidirectional"))
      (node (ref "S10") (pin "P$3") (pinfunction "3_P$3") (pintype "bidirectional"))
      (node (ref "S10") (pin "P$4") (pinfunction "4_P$4") (pintype "bidirectional"))
      (node (ref "S11") (pin "P$3") (pinfunction "3_P$3") (pintype "bidirectional"))
      (node (ref "S11") (pin "P$4") (pinfunction "4_P$4") (pintype "bidirectional"))
      (node (ref "S12") (pin "P$3") (pinfunction "3_P$3") (pintype "bidirectional"))
      (node (ref "S12") (pin "P$4") (pinfunction "4_P$4") (pintype "bidirectional"))
      (node (ref "S2") (pin "P$3") (pinfunction "3_P$3") (pintype "bidirectional"))
      (node (ref "S2") (pin "P$4") (pinfunction "4_P$4") (pintype "bidirectional"))
      (node (ref "S3") (pin "P$3") (pinfunction "3_P$3") (pintype "bidirectional"))
      (node (ref "S3") (pin "P$4") (pinfunction "4_P$4") (pintype "bidirectional"))
      (node (ref "S4") (pin "P$3") (pinfunction "3_P$3") (pintype "bidirectional"))
      (node (ref "S4") (pin "P$4") (pinfunction "4_P$4") (pintype "bidirectional"))
      (node (ref "S5") (pin "P$3") (pinfunction "3_P$3") (pintype "bidirectional"))
      (node (ref "S5") (pin "P$4") (pinfunction "4_P$4") (pintype "bidirectional"))
      (node (ref "S6") (pin "P$3") (pinfunction "3_P$3") (pintype "bidirectional"))
      (node (ref "S6") (pin "P$4") (pinfunction "4_P$4") (pintype "bidirectional"))
      (node (ref "S7") (pin "P$3") (pinfunction "3_P$3") (pintype "bidirectional"))
      (node (ref "S7") (pin "P$4") (pinfunction "4_P$4") (pintype "bidirectional"))
      (node (ref "S8") (pin "P$3") (pinfunction "3_P$3") (pintype "bidirectional"))
      (node (ref "S8") (pin "P$4") (pinfunction "4_P$4") (pintype "bidirectional"))
      (node (ref "S9") (pin "P$3") (pinfunction "3_P$3") (pintype "bidirectional"))
      (node (ref "S9") (pin "P$4") (pinfunction "4_P$4") (pintype "bidirectional"))
      (node (ref "TB7") (pin "P$1") (pinfunction "P$2_P$1") (pintype "bidirectional"))
    )
    (net (code "61") (name "Net-(JP1-Pad2)") (class "Default")
      (node (ref "JP1") (pin "2") (pinfunction "2_2") (pintype "passive"))
      (node (ref "PL1") (pin "MS3") (pinfunction "MS3_MS3") (pintype "bidirectional"))
    )
    (net (code "62") (name "Net-(JP1-Pad4)") (class "Default")
      (node (ref "JP1") (pin "4") (pinfunction "4_4") (pintype "passive"))
      (node (ref "PL1") (pin "MS2") (pinfunction "MS2_MS2") (pintype "bidirectional"))
    )
    (net (code "63") (name "Net-(JP1-Pad6)") (class "Default")
      (node (ref "JP1") (pin "6") (pinfunction "6_6") (pintype "passive"))
      (node (ref "PL1") (pin "MS1") (pinfunction "MS1_MS1") (pintype "bidirectional"))
    )
    (net (code "64") (name "Net-(JP2-Pad2)") (class "Default")
      (node (ref "JP2") (pin "2") (pinfunction "2_2") (pintype "passive"))
      (node (ref "PL2") (pin "MS3") (pinfunction "MS3_MS3") (pintype "bidirectional"))
    )
    (net (code "65") (name "Net-(JP2-Pad4)") (class "Default")
      (node (ref "JP2") (pin "4") (pinfunction "4_4") (pintype "passive"))
      (node (ref "PL2") (pin "MS2") (pinfunction "MS2_MS2") (pintype "bidirectional"))
    )
    (net (code "66") (name "Net-(JP2-Pad6)") (class "Default")
      (node (ref "JP2") (pin "6") (pinfunction "6_6") (pintype "passive"))
      (node (ref "PL2") (pin "MS1") (pinfunction "MS1_MS1") (pintype "bidirectional"))
    )
    (net (code "67") (name "Net-(JP3-Pad2)") (class "Default")
      (node (ref "JP3") (pin "2") (pinfunction "2_2") (pintype "passive"))
      (node (ref "PL3") (pin "MS3") (pinfunction "MS3_MS3") (pintype "bidirectional"))
    )
    (net (code "68") (name "Net-(JP3-Pad4)") (class "Default")
      (node (ref "JP3") (pin "4") (pinfunction "4_4") (pintype "passive"))
      (node (ref "PL3") (pin "MS2") (pinfunction "MS2_MS2") (pintype "bidirectional"))
    )
    (net (code "69") (name "Net-(JP3-Pad6)") (class "Default")
      (node (ref "JP3") (pin "6") (pinfunction "6_6") (pintype "passive"))
      (node (ref "PL3") (pin "MS1") (pinfunction "MS1_MS1") (pintype "bidirectional"))
    )
    (net (code "70") (name "Net-(JP10-Pad2)") (class "Default")
      (node (ref "JP10") (pin "2") (pinfunction "2_2") (pintype "passive"))
      (node (ref "PL4") (pin "MS3") (pinfunction "MS3_MS3") (pintype "bidirectional"))
    )
    (net (code "71") (name "Net-(JP10-Pad4)") (class "Default")
      (node (ref "JP10") (pin "4") (pinfunction "4_4") (pintype "passive"))
      (node (ref "PL4") (pin "MS2") (pinfunction "MS2_MS2") (pintype "bidirectional"))
    )
    (net (code "72") (name "Net-(JP10-Pad6)") (class "Default")
      (node (ref "JP10") (pin "6") (pinfunction "6_6") (pintype "passive"))
      (node (ref "PL4") (pin "MS1") (pinfunction "MS1_MS1") (pintype "bidirectional"))
    )
    (net (code "73") (name "Net-(JP11-Pad2)") (class "Default")
      (node (ref "JP11") (pin "2") (pinfunction "2_2") (pintype "passive"))
      (node (ref "PL5") (pin "MS3") (pinfunction "MS3_MS3") (pintype "bidirectional"))
    )
    (net (code "74") (name "Net-(JP11-Pad4)") (class "Default")
      (node (ref "JP11") (pin "4") (pinfunction "4_4") (pintype "passive"))
      (node (ref "PL5") (pin "MS2") (pinfunction "MS2_MS2") (pintype "bidirectional"))
    )
    (net (code "75") (name "Net-(JP11-Pad6)") (class "Default")
      (node (ref "JP11") (pin "6") (pinfunction "6_6") (pintype "passive"))
      (node (ref "PL5") (pin "MS1") (pinfunction "MS1_MS1") (pintype "bidirectional"))
    )
    (net (code "76") (name "Net-(JP12-Pad2)") (class "Default")
      (node (ref "JP12") (pin "2") (pinfunction "2_2") (pintype "passive"))
      (node (ref "PL6") (pin "MS3") (pinfunction "MS3_MS3") (pintype "bidirectional"))
    )
    (net (code "77") (name "Net-(JP12-Pad4)") (class "Default")
      (node (ref "JP12") (pin "4") (pinfunction "4_4") (pintype "passive"))
      (node (ref "PL6") (pin "MS2") (pinfunction "MS2_MS2") (pintype "bidirectional"))
    )
    (net (code "78") (name "Net-(JP12-Pad6)") (class "Default")
      (node (ref "JP12") (pin "6") (pinfunction "6_6") (pintype "passive"))
      (node (ref "PL6") (pin "MS1") (pinfunction "MS1_MS1") (pintype "bidirectional"))
    )
    (net (code "79") (name "Net-(L1-Pad1)") (class "Default")
      (node (ref "L1") (pin "1") (pinfunction "1_1") (pintype "passive"))
      (node (ref "PS1") (pin "P$2") (pinfunction "P$2_P$2") (pintype "bidirectional"))
    )
    (net (code "80") (name "Net-(LED1-PadC)") (class "Default")
      (node (ref "LED1") (pin "C") (pinfunction "C_C") (pintype "passive"))
      (node (ref "R4") (pin "1") (pinfunction "1_1") (pintype "passive"))
    )
    (net (code "81") (name "Net-(LED2-PadC)") (class "Default")
      (node (ref "LED2") (pin "C") (pinfunction "C_C") (pintype "passive"))
      (node (ref "R5") (pin "1") (pinfunction "1_1") (pintype "passive"))
    )
    (net (code "82") (name "Net-(LED3-PadC)") (class "Default")
      (node (ref "LED3") (pin "C") (pinfunction "C_C") (pintype "passive"))
      (node (ref "R6") (pin "1") (pinfunction "1_1") (pintype "passive"))
    )
    (net (code "83") (name "Net-(LED4-PadC)") (class "Default")
      (node (ref "LED4") (pin "C") (pinfunction "C_C") (pintype "passive"))
      (node (ref "R1") (pin "1") (pinfunction "1_1") (pintype "passive"))
    )
    (net (code "84") (name "Net-(LED5-PadC)") (class "Default")
      (node (ref "LED5") (pin "C") (pinfunction "C_C") (pintype "passive"))
      (node (ref "R2") (pin "1") (pinfunction "1_1") (pintype "passive"))
    )
    (net (code "85") (name "Net-(LED6-PadC)") (class "Default")
      (node (ref "LED6") (pin "C") (pinfunction "C_C") (pintype "passive"))
      (node (ref "R3") (pin "1") (pinfunction "1_1") (pintype "passive"))
    )
    (net (code "86") (name "Net-(LED7-PadC)") (class "Default")
      (node (ref "LED7") (pin "C") (pinfunction "C_C") (pintype "passive"))
      (node (ref "R7") (pin "1") (pinfunction "1_1") (pintype "passive"))
    )
    (net (code "87") (name "Net-(LED8-PadC)") (class "Default")
      (node (ref "LED8") (pin "C") (pinfunction "C_C") (pintype "passive"))
      (node (ref "R8") (pin "1") (pinfunction "1_1") (pintype "passive"))
    )
    (net (code "88") (name "Net-(LED9-PadC)") (class "Default")
      (node (ref "LED9") (pin "C") (pinfunction "C_C") (pintype "passive"))
      (node (ref "R12") (pin "1") (pinfunction "1_1") (pintype "passive"))
    )
    (net (code "89") (name "Net-(LED10-PadC)") (class "Default")
      (node (ref "LED10") (pin "C") (pinfunction "C_C") (pintype "passive"))
      (node (ref "R13") (pin "1") (pinfunction "1_1") (pintype "passive"))
    )
    (net (code "90") (name "Net-(LED11-PadC)") (class "Default")
      (node (ref "LED11") (pin "C") (pinfunction "C_C") (pintype "passive"))
      (node (ref "R14") (pin "1") (pinfunction "1_1") (pintype "passive"))
    )
    (net (code "91") (name "Net-(LED12-PadC)") (class "Default")
      (node (ref "LED12") (pin "C") (pinfunction "C_C") (pintype "passive"))
      (node (ref "R9") (pin "1") (pinfunction "1_1") (pintype "passive"))
    )
    (net (code "92") (name "Net-(LED13-PadC)") (class "Default")
      (node (ref "LED13") (pin "C") (pinfunction "C_C") (pintype "passive"))
      (node (ref "R10") (pin "1") (pinfunction "1_1") (pintype "passive"))
    )
    (net (code "93") (name "Net-(LED14-PadC)") (class "Default")
      (node (ref "LED14") (pin "C") (pinfunction "C_C") (pintype "passive"))
      (node (ref "R11") (pin "1") (pinfunction "1_1") (pintype "passive"))
    )
    (net (code "94") (name "Net-(PL1-Pad1A)") (class "Default")
      (node (ref "PL1") (pin "1A") (pinfunction "1A_1A") (pintype "bidirectional"))
      (node (ref "TB1") (pin "P$3") (pinfunction "P$3_P$3") (pintype "bidirectional"))
    )
    (net (code "95") (name "Net-(PL1-Pad1B)") (class "Default")
      (node (ref "PL1") (pin "1B") (pinfunction "1B_1B") (pintype "bidirectional"))
      (node (ref "TB1") (pin "P$4") (pinfunction "P$4_P$4") (pintype "bidirectional"))
    )
    (net (code "96") (name "Net-(PL1-Pad2A)") (class "Default")
      (node (ref "PL1") (pin "2A") (pinfunction "2A_2A") (pintype "bidirectional"))
      (node (ref "TB1") (pin "P$2") (pinfunction "P$2_P$2") (pintype "bidirectional"))
    )
    (net (code "97") (name "Net-(PL1-Pad2B)") (class "Default")
      (node (ref "PL1") (pin "2B") (pinfunction "2B_2B") (pintype "bidirectional"))
      (node (ref "TB1") (pin "P$1") (pinfunction "P$1_P$1") (pintype "bidirectional"))
    )
    (net (code "98") (name "Net-(PL1-~{RST})") (class "Default")
      (node (ref "PL1") (pin "!RST") (pinfunction "~{RST}_!RST") (pintype "bidirectional"))
      (node (ref "PL1") (pin "!SLP") (pinfunction "~{SLP}_!SLP") (pintype "bidirectional"))
    )
    (net (code "99") (name "Net-(PL2-Pad1A)") (class "Default")
      (node (ref "PL2") (pin "1A") (pinfunction "1A_1A") (pintype "bidirectional"))
      (node (ref "TB2") (pin "P$3") (pinfunction "P$3_P$3") (pintype "bidirectional"))
    )
    (net (code "100") (name "Net-(PL2-Pad1B)") (class "Default")
      (node (ref "PL2") (pin "1B") (pinfunction "1B_1B") (pintype "bidirectional"))
      (node (ref "TB2") (pin "P$4") (pinfunction "P$4_P$4") (pintype "bidirectional"))
    )
    (net (code "101") (name "Net-(PL2-Pad2A)") (class "Default")
      (node (ref "PL2") (pin "2A") (pinfunction "2A_2A") (pintype "bidirectional"))
      (node (ref "TB2") (pin "P$2") (pinfunction "P$2_P$2") (pintype "bidirectional"))
    )
    (net (code "102") (name "Net-(PL2-Pad2B)") (class "Default")
      (node (ref "PL2") (pin "2B") (pinfunction "2B_2B") (pintype "bidirectional"))
      (node (ref "TB2") (pin "P$1") (pinfunction "P$1_P$1") (pintype "bidirectional"))
    )
    (net (code "103") (name "Net-(PL2-~{RST})") (class "Default")
      (node (ref "PL2") (pin "!RST") (pinfunction "~{RST}_!RST") (pintype "bidirectional"))
      (node (ref "PL2") (pin "!SLP") (pinfunction "~{SLP}_!SLP") (pintype "bidirectional"))
    )
    (net (code "104") (name "Net-(PL3-Pad1A)") (class "Default")
      (node (ref "PL3") (pin "1A") (pinfunction "1A_1A") (pintype "bidirectional"))
      (node (ref "TB3") (pin "P$3") (pinfunction "P$3_P$3") (pintype "bidirectional"))
    )
    (net (code "105") (name "Net-(PL3-Pad1B)") (class "Default")
      (node (ref "PL3") (pin "1B") (pinfunction "1B_1B") (pintype "bidirectional"))
      (node (ref "TB3") (pin "P$4") (pinfunction "P$4_P$4") (pintype "bidirectional"))
    )
    (net (code "106") (name "Net-(PL3-Pad2A)") (class "Default")
      (node (ref "PL3") (pin "2A") (pinfunction "2A_2A") (pintype "bidirectional"))
      (node (ref "TB3") (pin "P$2") (pinfunction "P$2_P$2") (pintype "bidirectional"))
    )
    (net (code "107") (name "Net-(PL3-Pad2B)") (class "Default")
      (node (ref "PL3") (pin "2B") (pinfunction "2B_2B") (pintype "bidirectional"))
      (node (ref "TB3") (pin "P$1") (pinfunction "P$1_P$1") (pintype "bidirectional"))
    )
    (net (code "108") (name "Net-(PL3-~{RST})") (class "Default")
      (node (ref "PL3") (pin "!RST") (pinfunction "~{RST}_!RST") (pintype "bidirectional"))
      (node (ref "PL3") (pin "!SLP") (pinfunction "~{SLP}_!SLP") (pintype "bidirectional"))
    )
    (net (code "109") (name "Net-(PL4-Pad1A)") (class "Default")
      (node (ref "PL4") (pin "1A") (pinfunction "1A_1A") (pintype "bidirectional"))
      (node (ref "TB4") (pin "P$3") (pinfunction "P$3_P$3") (pintype "bidirectional"))
    )
    (net (code "110") (name "Net-(PL4-Pad1B)") (class "Default")
      (node (ref "PL4") (pin "1B") (pinfunction "1B_1B") (pintype "bidirectional"))
      (node (ref "TB4") (pin "P$4") (pinfunction "P$4_P$4") (pintype "bidirectional"))
    )
    (net (code "111") (name "Net-(PL4-Pad2A)") (class "Default")
      (node (ref "PL4") (pin "2A") (pinfunction "2A_2A") (pintype "bidirectional"))
      (node (ref "TB4") (pin "P$2") (pinfunction "P$2_P$2") (pintype "bidirectional"))
    )
    (net (code "112") (name "Net-(PL4-Pad2B)") (class "Default")
      (node (ref "PL4") (pin "2B") (pinfunction "2B_2B") (pintype "bidirectional"))
      (node (ref "TB4") (pin "P$1") (pinfunction "P$1_P$1") (pintype "bidirectional"))
    )
    (net (code "113") (name "Net-(PL4-~{RST})") (class "Default")
      (node (ref "PL4") (pin "!RST") (pinfunction "~{RST}_!RST") (pintype "bidirectional"))
      (node (ref "PL4") (pin "!SLP") (pinfunction "~{SLP}_!SLP") (pintype "bidirectional"))
    )
    (net (code "114") (name "Net-(PL5-Pad1A)") (class "Default")
      (node (ref "PL5") (pin "1A") (pinfunction "1A_1A") (pintype "bidirectional"))
      (node (ref "TB5") (pin "P$3") (pinfunction "P$3_P$3") (pintype "bidirectional"))
    )
    (net (code "115") (name "Net-(PL5-Pad1B)") (class "Default")
      (node (ref "PL5") (pin "1B") (pinfunction "1B_1B") (pintype "bidirectional"))
      (node (ref "TB5") (pin "P$4") (pinfunction "P$4_P$4") (pintype "bidirectional"))
    )
    (net (code "116") (name "Net-(PL5-Pad2A)") (class "Default")
      (node (ref "PL5") (pin "2A") (pinfunction "2A_2A") (pintype "bidirectional"))
      (node (ref "TB5") (pin "P$2") (pinfunction "P$2_P$2") (pintype "bidirectional"))
    )
    (net (code "117") (name "Net-(PL5-Pad2B)") (class "Default")
      (node (ref "PL5") (pin "2B") (pinfunction "2B_2B") (pintype "bidirectional"))
      (node (ref "TB5") (pin "P$1") (pinfunction "P$1_P$1") (pintype "bidirectional"))
    )
    (net (code "118") (name "Net-(PL5-~{RST})") (class "Default")
      (node (ref "PL5") (pin "!RST") (pinfunction "~{RST}_!RST") (pintype "bidirectional"))
      (node (ref "PL5") (pin "!SLP") (pinfunction "~{SLP}_!SLP") (pintype "bidirectional"))
    )
    (net (code "119") (name "Net-(PL6-Pad1A)") (class "Default")
      (node (ref "PL6") (pin "1A") (pinfunction "1A_1A") (pintype "bidirectional"))
      (node (ref "TB6") (pin "P$3") (pinfunction "P$3_P$3") (pintype "bidirectional"))
    )
    (net (code "120") (name "Net-(PL6-Pad1B)") (class "Default")
      (node (ref "PL6") (pin "1B") (pinfunction "1B_1B") (pintype "bidirectional"))
      (node (ref "TB6") (pin "P$4") (pinfunction "P$4_P$4") (pintype "bidirectional"))
    )
    (net (code "121") (name "Net-(PL6-Pad2A)") (class "Default")
      (node (ref "PL6") (pin "2A") (pinfunction "2A_2A") (pintype "bidirectional"))
      (node (ref "TB6") (pin "P$2") (pinfunction "P$2_P$2") (pintype "bidirectional"))
    )
    (net (code "122") (name "Net-(PL6-Pad2B)") (class "Default")
      (node (ref "PL6") (pin "2B") (pinfunction "2B_2B") (pintype "bidirectional"))
      (node (ref "TB6") (pin "P$1") (pinfunction "P$1_P$1") (pintype "bidirectional"))
    )
    (net (code "123") (name "Net-(PL6-~{RST})") (class "Default")
      (node (ref "PL6") (pin "!RST") (pinfunction "~{RST}_!RST") (pintype "bidirectional"))
      (node (ref "PL6") (pin "!SLP") (pinfunction "~{SLP}_!SLP") (pintype "bidirectional"))
    )
    (net (code "124") (name "unconnected-(DUE1-Pad5V_A)") (class "Default")
      (node (ref "DUE1") (pin "5V_A") (pinfunction "5V_A_5V_A") (pintype "bidirectional"))
    )
    (net (code "125") (name "unconnected-(DUE1-Pad5V_B)") (class "Default")
      (node (ref "DUE1") (pin "5V_B") (pinfunction "5V_B_5V_B") (pintype "bidirectional"))
    )
    (net (code "126") (name "unconnected-(DUE1-Pad22)") (class "Default")
      (node (ref "DUE1") (pin "22") (pinfunction "22_22") (pintype "bidirectional"))
    )
    (net (code "127") (name "unconnected-(DUE1-Pad23)") (class "Default")
      (node (ref "DUE1") (pin "23") (pinfunction "23_23") (pintype "bidirectional"))
    )
    (net (code "128") (name "unconnected-(DUE1-PadA6)") (class "Default")
      (node (ref "DUE1") (pin "A6") (pinfunction "A6_A6") (pintype "bidirectional"))
    )
    (net (code "129") (name "unconnected-(DUE1-PadA7)") (class "Default")
      (node (ref "DUE1") (pin "A7") (pinfunction "A7_A7") (pintype "bidirectional"))
    )
    (net (code "130") (name "unconnected-(DUE1-PadA8)") (class "Default")
      (node (ref "DUE1") (pin "A8") (pinfunction "A8_A8") (pintype "bidirectional"))
    )
    (net (code "131") (name "unconnected-(DUE1-PadA9)") (class "Default")
      (node (ref "DUE1") (pin "A9") (pinfunction "A9_A9") (pintype "bidirectional"))
    )
    (net (code "132") (name "unconnected-(DUE1-PadA10)") (class "Default")
      (node (ref "DUE1") (pin "A10") (pinfunction "A10_A10") (pintype "bidirectional"))
    )
    (net (code "133") (name "unconnected-(DUE1-PadA11)") (class "Default")
      (node (ref "DUE1") (pin "A11") (pinfunction "A11_A11") (pintype "bidirectional"))
    )
    (net (code "134") (name "unconnected-(DUE1-PadAREF)") (class "Default")
      (node (ref "DUE1") (pin "AREF") (pinfunction "AREF_AREF") (pintype "bidirectional"))
    )
    (net (code "135") (name "unconnected-(DUE1-PadCANRX)") (class "Default")
      (node (ref "DUE1") (pin "CANRX") (pinfunction "CANRX_CANRX") (pintype "bidirectional"))
    )
    (net (code "136") (name "unconnected-(DUE1-PadCANTX)") (class "Default")
      (node (ref "DUE1") (pin "CANTX") (pinfunction "CANTX_CANTX") (pintype "bidirectional"))
    )
    (net (code "137") (name "unconnected-(DUE1-PadDAC0)") (class "Default")
      (node (ref "DUE1") (pin "DAC0") (pinfunction "DAC0_DAC0") (pintype "bidirectional"))
    )
    (net (code "138") (name "unconnected-(DUE1-PadDAC1)") (class "Default")
      (node (ref "DUE1") (pin "DAC1") (pinfunction "DAC1_DAC1") (pintype "bidirectional"))
    )
    (net (code "139") (name "unconnected-(DUE1-PadGND1)") (class "Default")
      (node (ref "DUE1") (pin "GND1") (pinfunction "GND1_GND1") (pintype "bidirectional"))
    )
    (net (code "140") (name "unconnected-(DUE1-PadIOREF)") (class "Default")
      (node (ref "DUE1") (pin "IOREF") (pinfunction "IOREF_IOREF") (pintype "bidirectional"))
    )
    (net (code "141") (name "unconnected-(DUE1-PadNC)") (class "Default")
      (node (ref "DUE1") (pin "NC") (pinfunction "NC_NC") (pintype "bidirectional"))
    )
    (net (code "142") (name "unconnected-(DUE1-PadRESET)") (class "Default")
      (node (ref "DUE1") (pin "RESET") (pinfunction "RESET_RESET") (pintype "bidirectional"))
    )
    (net (code "143") (name "unconnected-(DUE1-PadRX0)") (class "Default")
      (node (ref "DUE1") (pin "RX0") (pinfunction "RX0_RX0") (pintype "bidirectional"))
    )
    (net (code "144") (name "unconnected-(DUE1-PadSCL)") (class "Default")
      (node (ref "DUE1") (pin "SCL") (pinfunction "SCL_SCL") (pintype "bidirectional"))
    )
    (net (code "145") (name "unconnected-(DUE1-PadSCL1)") (class "Default")
      (node (ref "DUE1") (pin "SCL1") (pinfunction "SCL1_SCL1") (pintype "bidirectional"))
    )
    (net (code "146") (name "unconnected-(DUE1-PadSDA)") (class "Default")
      (node (ref "DUE1") (pin "SDA") (pinfunction "SDA_SDA") (pintype "bidirectional"))
    )
    (net (code "147") (name "unconnected-(DUE1-PadSDA1)") (class "Default")
      (node (ref "DUE1") (pin "SDA1") (pinfunction "SDA1_SDA1") (pintype "bidirectional"))
    )
    (net (code "148") (name "unconnected-(DUE1-PadTX0)") (class "Default")
      (node (ref "DUE1") (pin "TX0") (pinfunction "TX0_TX0") (pintype "bidirectional"))
    )
  )
)
